# PCIE_PACKET_SWITCH.net
KiCad netlist of a schematic drawn in Altium Designer
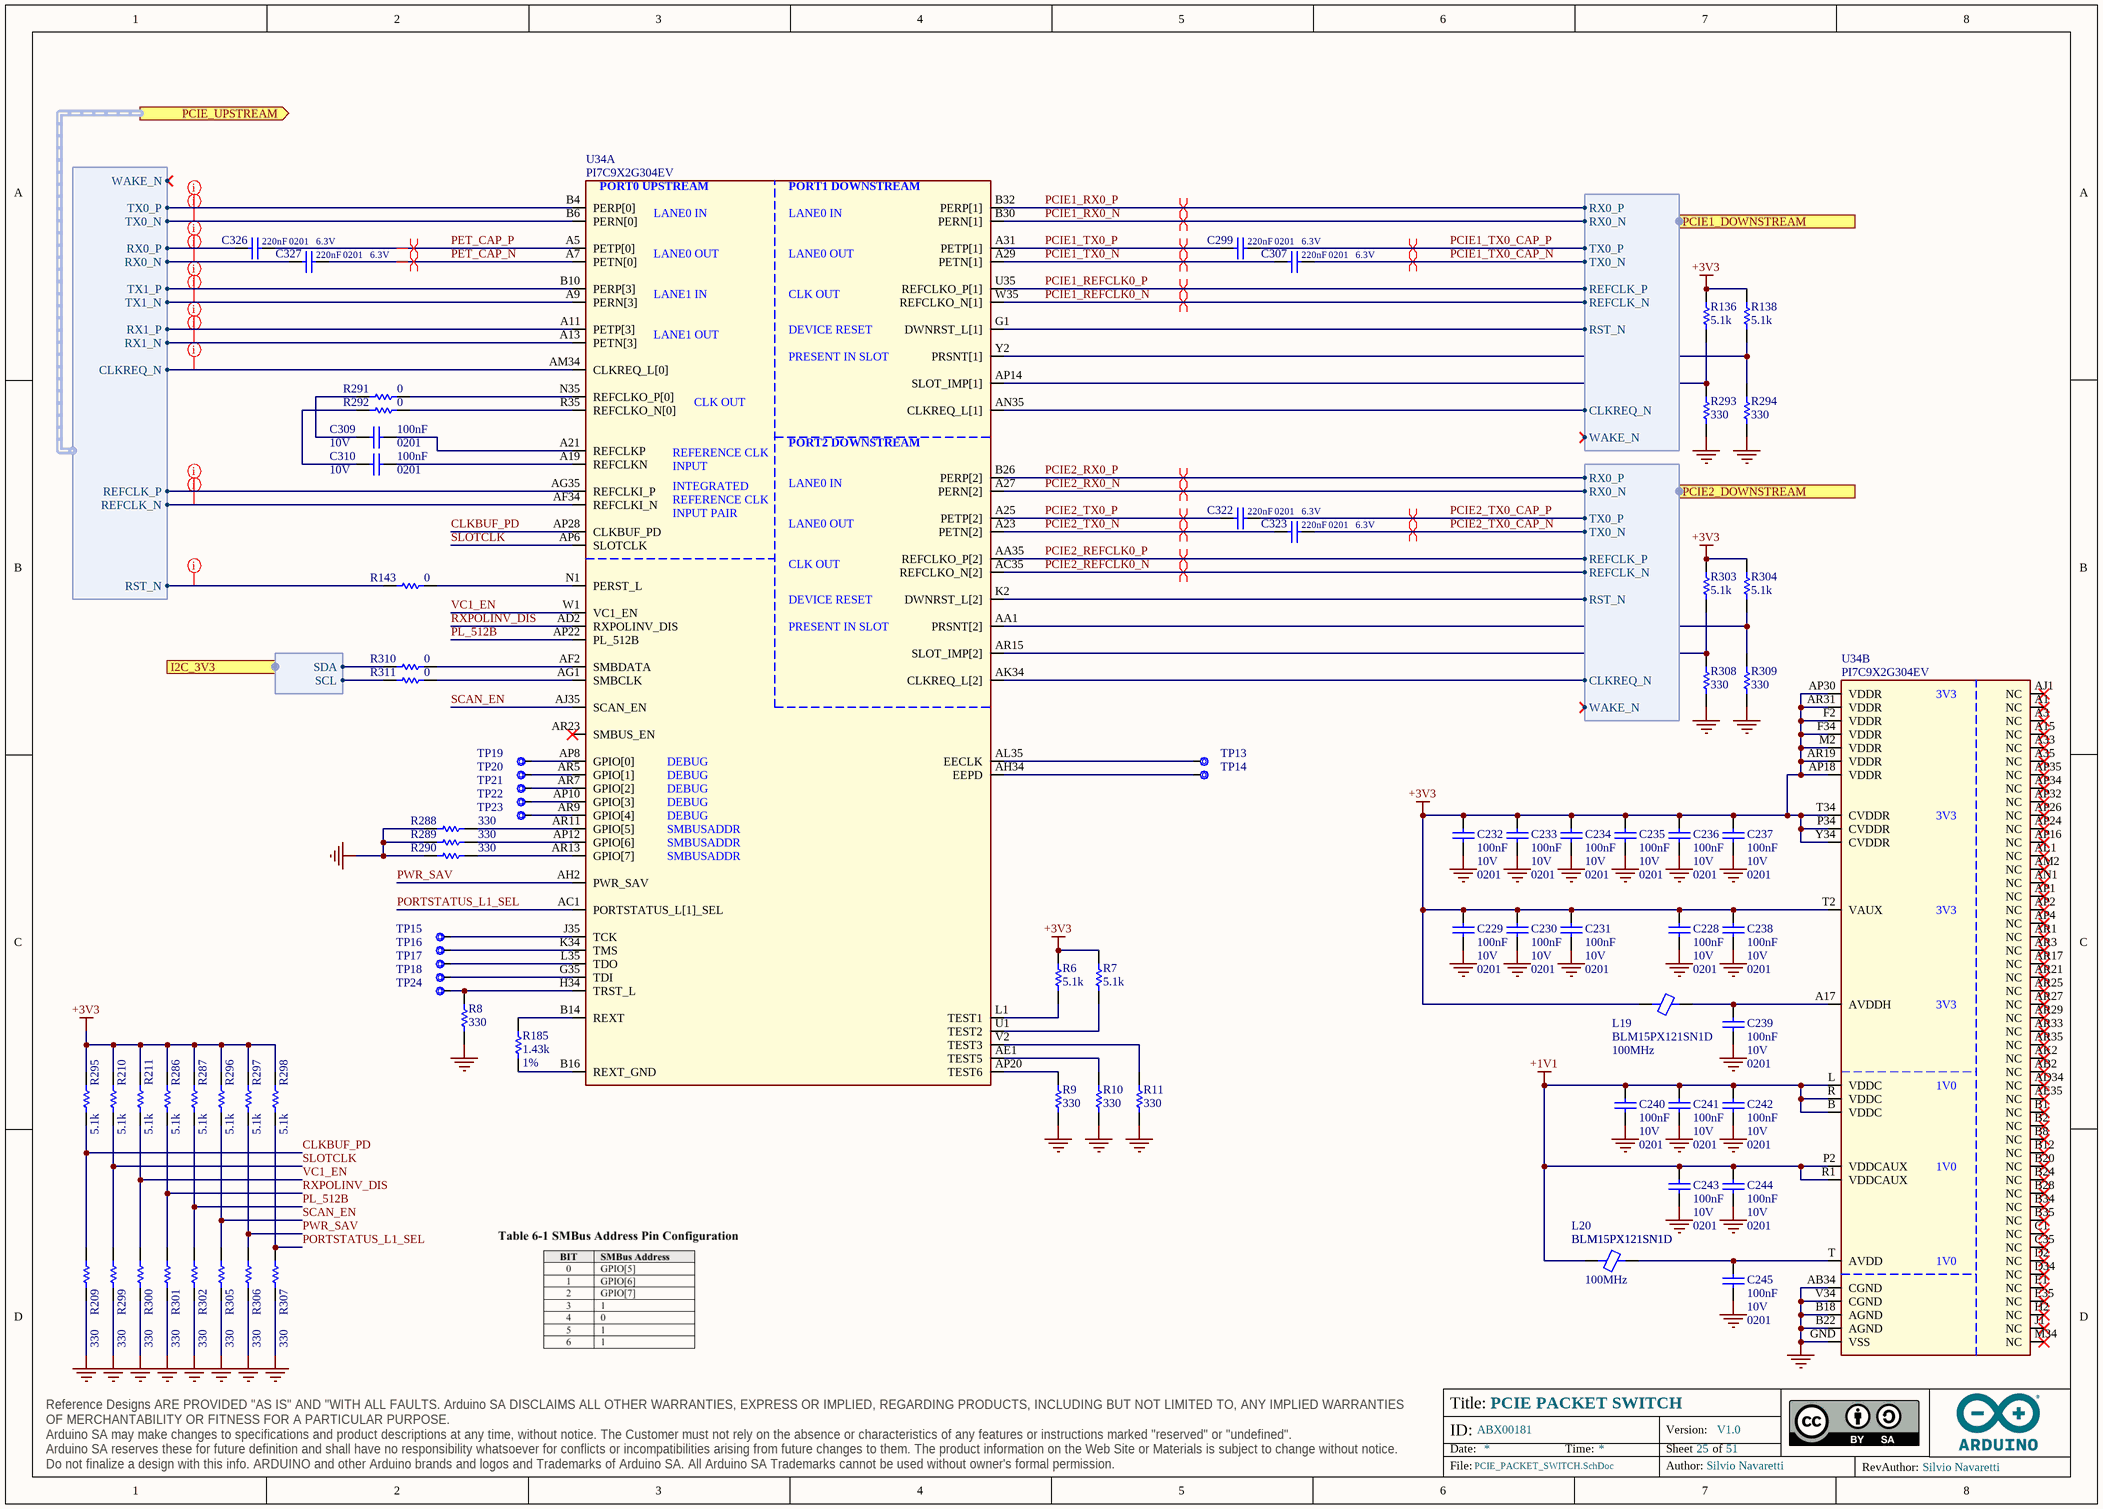
[diagram p0: PCIE_PACKET_SWITCH.SchDoc]

(export (version "E")
  (design (tool "Eeschema 10.0.6"))
  (components
    (comp (ref "C228")
      (value "100nF")
      (footprint "CAP-0201")
      (description "CAP CHIP 0201 100nF 10% 10V X5R")
      (fields
        (field (name "PART NUMBER") "CL03A104KP3NNNC")
        (field (name "MANUFACTURER") "Samsung Electro-Mechanics")
        (field (name "VOLTAGE") "10V")
        (field (name "CASE CODE (IMPERIAL)") "0201")
      )
      (libsource (lib "Clean") (part "CAP"))
    )
    (comp (ref "C229")
      (value "100nF")
      (footprint "CAP-0201")
      (description "CAP CHIP 0201 100nF 10% 10V X5R")
      (fields
        (field (name "PART NUMBER") "CL03A104KP3NNNC")
        (field (name "MANUFACTURER") "Samsung Electro-Mechanics")
        (field (name "VOLTAGE") "10V")
        (field (name "CASE CODE (IMPERIAL)") "0201")
      )
      (libsource (lib "Clean") (part "CAP"))
    )
    (comp (ref "C230")
      (value "100nF")
      (footprint "CAP-0201")
      (description "CAP CHIP 0201 100nF 10% 10V X5R")
      (fields
        (field (name "PART NUMBER") "CL03A104KP3NNNC")
        (field (name "MANUFACTURER") "Samsung Electro-Mechanics")
        (field (name "VOLTAGE") "10V")
        (field (name "CASE CODE (IMPERIAL)") "0201")
      )
      (libsource (lib "Clean") (part "CAP"))
    )
    (comp (ref "C231")
      (value "100nF")
      (footprint "CAP-0201")
      (description "CAP CHIP 0201 100nF 10% 10V X5R")
      (fields
        (field (name "PART NUMBER") "CL03A104KP3NNNC")
        (field (name "MANUFACTURER") "Samsung Electro-Mechanics")
        (field (name "VOLTAGE") "10V")
        (field (name "CASE CODE (IMPERIAL)") "0201")
      )
      (libsource (lib "Clean") (part "CAP"))
    )
    (comp (ref "C232")
      (value "100nF")
      (footprint "CAP-0201")
      (description "CAP CHIP 0201 100nF 10% 10V X5R")
      (fields
        (field (name "PART NUMBER") "CL03A104KP3NNNC")
        (field (name "MANUFACTURER") "Samsung Electro-Mechanics")
        (field (name "VOLTAGE") "10V")
        (field (name "CASE CODE (IMPERIAL)") "0201")
      )
      (libsource (lib "Clean") (part "CAP"))
    )
    (comp (ref "C233")
      (value "100nF")
      (footprint "CAP-0201")
      (description "CAP CHIP 0201 100nF 10% 10V X5R")
      (fields
        (field (name "PART NUMBER") "CL03A104KP3NNNC")
        (field (name "MANUFACTURER") "Samsung Electro-Mechanics")
        (field (name "VOLTAGE") "10V")
        (field (name "CASE CODE (IMPERIAL)") "0201")
      )
      (libsource (lib "Clean") (part "CAP"))
    )
    (comp (ref "C234")
      (value "100nF")
      (footprint "CAP-0201")
      (description "CAP CHIP 0201 100nF 10% 10V X5R")
      (fields
        (field (name "PART NUMBER") "CL03A104KP3NNNC")
        (field (name "MANUFACTURER") "Samsung Electro-Mechanics")
        (field (name "VOLTAGE") "10V")
        (field (name "CASE CODE (IMPERIAL)") "0201")
      )
      (libsource (lib "Clean") (part "CAP"))
    )
    (comp (ref "C235")
      (value "100nF")
      (footprint "CAP-0201")
      (description "CAP CHIP 0201 100nF 10% 10V X5R")
      (fields
        (field (name "PART NUMBER") "CL03A104KP3NNNC")
        (field (name "MANUFACTURER") "Samsung Electro-Mechanics")
        (field (name "VOLTAGE") "10V")
        (field (name "CASE CODE (IMPERIAL)") "0201")
      )
      (libsource (lib "Clean") (part "CAP"))
    )
    (comp (ref "C236")
      (value "100nF")
      (footprint "CAP-0201")
      (description "CAP CHIP 0201 100nF 10% 10V X5R")
      (fields
        (field (name "PART NUMBER") "CL03A104KP3NNNC")
        (field (name "MANUFACTURER") "Samsung Electro-Mechanics")
        (field (name "VOLTAGE") "10V")
        (field (name "CASE CODE (IMPERIAL)") "0201")
      )
      (libsource (lib "Clean") (part "CAP"))
    )
    (comp (ref "C237")
      (value "100nF")
      (footprint "CAP-0201")
      (description "CAP CHIP 0201 100nF 10% 10V X5R")
      (fields
        (field (name "PART NUMBER") "CL03A104KP3NNNC")
        (field (name "MANUFACTURER") "Samsung Electro-Mechanics")
        (field (name "VOLTAGE") "10V")
        (field (name "CASE CODE (IMPERIAL)") "0201")
      )
      (libsource (lib "Clean") (part "CAP"))
    )
    (comp (ref "C238")
      (value "100nF")
      (footprint "CAP-0201")
      (description "CAP CHIP 0201 100nF 10% 10V X5R")
      (fields
        (field (name "PART NUMBER") "CL03A104KP3NNNC")
        (field (name "MANUFACTURER") "Samsung Electro-Mechanics")
        (field (name "VOLTAGE") "10V")
        (field (name "CASE CODE (IMPERIAL)") "0201")
      )
      (libsource (lib "Clean") (part "CAP"))
    )
    (comp (ref "C239")
      (value "100nF")
      (footprint "CAP-0201")
      (description "CAP CHIP 0201 100nF 10% 10V X5R")
      (fields
        (field (name "PART NUMBER") "CL03A104KP3NNNC")
        (field (name "MANUFACTURER") "Samsung Electro-Mechanics")
        (field (name "VOLTAGE") "10V")
        (field (name "CASE CODE (IMPERIAL)") "0201")
      )
      (libsource (lib "Clean") (part "CAP"))
    )
    (comp (ref "C240")
      (value "100nF")
      (footprint "CAP-0201")
      (description "CAP CHIP 0201 100nF 10% 10V X5R")
      (fields
        (field (name "PART NUMBER") "CL03A104KP3NNNC")
        (field (name "MANUFACTURER") "Samsung Electro-Mechanics")
        (field (name "VOLTAGE") "10V")
        (field (name "CASE CODE (IMPERIAL)") "0201")
      )
      (libsource (lib "Clean") (part "CAP"))
    )
    (comp (ref "C241")
      (value "100nF")
      (footprint "CAP-0201")
      (description "CAP CHIP 0201 100nF 10% 10V X5R")
      (fields
        (field (name "PART NUMBER") "CL03A104KP3NNNC")
        (field (name "MANUFACTURER") "Samsung Electro-Mechanics")
        (field (name "VOLTAGE") "10V")
        (field (name "CASE CODE (IMPERIAL)") "0201")
      )
      (libsource (lib "Clean") (part "CAP"))
    )
    (comp (ref "C242")
      (value "100nF")
      (footprint "CAP-0201")
      (description "CAP CHIP 0201 100nF 10% 10V X5R")
      (fields
        (field (name "PART NUMBER") "CL03A104KP3NNNC")
        (field (name "MANUFACTURER") "Samsung Electro-Mechanics")
        (field (name "VOLTAGE") "10V")
        (field (name "CASE CODE (IMPERIAL)") "0201")
      )
      (libsource (lib "Clean") (part "CAP"))
    )
    (comp (ref "C243")
      (value "100nF")
      (footprint "CAP-0201")
      (description "CAP CHIP 0201 100nF 10% 10V X5R")
      (fields
        (field (name "PART NUMBER") "CL03A104KP3NNNC")
        (field (name "MANUFACTURER") "Samsung Electro-Mechanics")
        (field (name "VOLTAGE") "10V")
        (field (name "CASE CODE (IMPERIAL)") "0201")
      )
      (libsource (lib "Clean") (part "CAP"))
    )
    (comp (ref "C244")
      (value "100nF")
      (footprint "CAP-0201")
      (description "CAP CHIP 0201 100nF 10% 10V X5R")
      (fields
        (field (name "PART NUMBER") "CL03A104KP3NNNC")
        (field (name "MANUFACTURER") "Samsung Electro-Mechanics")
        (field (name "VOLTAGE") "10V")
        (field (name "CASE CODE (IMPERIAL)") "0201")
      )
      (libsource (lib "Clean") (part "CAP"))
    )
    (comp (ref "C245")
      (value "100nF")
      (footprint "CAP-0201")
      (description "CAP CHIP 0201 100nF 10% 10V X5R")
      (fields
        (field (name "PART NUMBER") "CL03A104KP3NNNC")
        (field (name "MANUFACTURER") "Samsung Electro-Mechanics")
        (field (name "VOLTAGE") "10V")
        (field (name "CASE CODE (IMPERIAL)") "0201")
      )
      (libsource (lib "Clean") (part "CAP"))
    )
    (comp (ref "C299")
      (value "220nF")
      (footprint "CAP-0201")
      (description "CAP CHIP 0201 220nF 20% 6.3V X5R")
      (fields
        (field (name "CASE CODE (IMPERIAL)") "0201")
        (field (name "TOLERANCE") "20%")
        (field (name "PART NUMBER") "GRM033R60J224ME15D")
        (field (name "VOLTAGE") "6.3V")
      )
      (libsource (lib "Clean") (part "CAP"))
    )
    (comp (ref "C307")
      (value "220nF")
      (footprint "CAP-0201")
      (description "CAP CHIP 0201 220nF 20% 6.3V X5R")
      (fields
        (field (name "CASE CODE (IMPERIAL)") "0201")
        (field (name "TOLERANCE") "20%")
        (field (name "PART NUMBER") "GRM033R60J224ME15D")
        (field (name "VOLTAGE") "6.3V")
      )
      (libsource (lib "Clean") (part "CAP"))
    )
    (comp (ref "C309")
      (value "100nF")
      (footprint "CAP-0201")
      (description "CAP CHIP 0201 100nF 10% 10V X5R")
      (fields
        (field (name "PART NUMBER") "CL03A104KP3NNNC")
        (field (name "MANUFACTURER") "Samsung Electro-Mechanics")
        (field (name "VOLTAGE") "10V")
        (field (name "CASE CODE (IMPERIAL)") "0201")
      )
      (libsource (lib "Clean") (part "CAP"))
    )
    (comp (ref "C310")
      (value "100nF")
      (footprint "CAP-0201")
      (description "CAP CHIP 0201 100nF 10% 10V X5R")
      (fields
        (field (name "PART NUMBER") "CL03A104KP3NNNC")
        (field (name "MANUFACTURER") "Samsung Electro-Mechanics")
        (field (name "VOLTAGE") "10V")
        (field (name "CASE CODE (IMPERIAL)") "0201")
      )
      (libsource (lib "Clean") (part "CAP"))
    )
    (comp (ref "C322")
      (value "220nF")
      (footprint "CAP-0201")
      (description "CAP CHIP 0201 220nF 20% 6.3V X5R")
      (fields
        (field (name "CASE CODE (IMPERIAL)") "0201")
        (field (name "TOLERANCE") "20%")
        (field (name "PART NUMBER") "GRM033R60J224ME15D")
        (field (name "VOLTAGE") "6.3V")
      )
      (libsource (lib "Clean") (part "CAP"))
    )
    (comp (ref "C323")
      (value "220nF")
      (footprint "CAP-0201")
      (description "CAP CHIP 0201 220nF 20% 6.3V X5R")
      (fields
        (field (name "CASE CODE (IMPERIAL)") "0201")
        (field (name "TOLERANCE") "20%")
        (field (name "PART NUMBER") "GRM033R60J224ME15D")
        (field (name "VOLTAGE") "6.3V")
      )
      (libsource (lib "Clean") (part "CAP"))
    )
    (comp (ref "C326")
      (value "220nF")
      (footprint "CAP-0201")
      (description "CAP CHIP 0201 220nF 20% 6.3V X5R")
      (fields
        (field (name "CASE CODE (IMPERIAL)") "0201")
        (field (name "TOLERANCE") "20%")
        (field (name "PART NUMBER") "GRM033R60J224ME15D")
        (field (name "VOLTAGE") "6.3V")
      )
      (libsource (lib "Clean") (part "CAP"))
    )
    (comp (ref "C327")
      (value "220nF")
      (footprint "CAP-0201")
      (description "CAP CHIP 0201 220nF 20% 6.3V X5R")
      (fields
        (field (name "CASE CODE (IMPERIAL)") "0201")
        (field (name "TOLERANCE") "20%")
        (field (name "PART NUMBER") "GRM033R60J224ME15D")
        (field (name "VOLTAGE") "6.3V")
      )
      (libsource (lib "Clean") (part "CAP"))
    )
    (comp (ref "L19")
      (value "BLM15PX121SN1D")
      (footprint "L-0402")
      (description "FERRITE SMD 0402 120Ohm 25% 100MHz Ferrite 2A")
      (fields
        (field (name "TEST FREQUENCY") "100MHz")
        (field (name "MANUFACTURER") "Murata")
        (field (name "TOLERANCE") "25%")
      )
      (libsource (lib "Clean") (part "Ferrite"))
    )
    (comp (ref "L20")
      (value "BLM15PX121SN1D")
      (footprint "L-0402")
      (description "FERRITE SMD 0402 120Ohm 25% 100MHz Ferrite 2A")
      (fields
        (field (name "PART NUMBER") "BLM15PX121SN1D")
        (field (name "TEST FREQUENCY") "100MHz")
        (field (name "MANUFACTURER") "Murata")
        (field (name "TOLERANCE") "25%")
      )
      (libsource (lib "Clean") (part "Ferrite"))
    )
    (comp (ref "R6")
      (value "5.1k")
      (footprint "RES-0201")
      (description "RES CHIP 0201 5k1 1% 1/20W")
      (fields (field (name "MANUFACTURER") "Panasonic") (field (name "PART NUMBER") "ERJ-1GNF5101C"))
      (libsource (lib "Clean") (part "RES"))
    )
    (comp (ref "R7")
      (value "5.1k")
      (footprint "RES-0201")
      (description "RES CHIP 0201 5k1 1% 1/20W")
      (fields (field (name "MANUFACTURER") "Panasonic") (field (name "PART NUMBER") "ERJ-1GNF5101C"))
      (libsource (lib "Clean") (part "RES"))
    )
    (comp (ref "R8")
      (value "330")
      (footprint "RES-0201")
      (description "RES CHIP 0201 330R 1% 1/20W")
      (fields (field (name "MANUFACTURER") "Yageo") (field (name "POWER") "50mW"))
      (libsource (lib "Clean") (part "RES"))
    )
    (comp (ref "R9")
      (value "330")
      (footprint "RES-0201")
      (description "RES CHIP 0201 330R 1% 1/20W")
      (fields (field (name "MANUFACTURER") "Yageo") (field (name "POWER") "50mW"))
      (libsource (lib "Clean") (part "RES"))
    )
    (comp (ref "R10")
      (value "330")
      (footprint "RES-0201")
      (description "RES CHIP 0201 330R 1% 1/20W")
      (fields (field (name "MANUFACTURER") "Yageo") (field (name "POWER") "50mW"))
      (libsource (lib "Clean") (part "RES"))
    )
    (comp (ref "R11")
      (value "330")
      (footprint "RES-0201")
      (description "RES CHIP 0201 330R 1% 1/20W")
      (fields (field (name "MANUFACTURER") "Yageo") (field (name "POWER") "50mW"))
      (libsource (lib "Clean") (part "RES"))
    )
    (comp (ref "R136")
      (value "5.1k")
      (footprint "RES-0201")
      (description "RES CHIP 0201 5k1 1% 1/20W")
      (fields (field (name "MANUFACTURER") "Panasonic") (field (name "PART NUMBER") "ERJ-1GNF5101C"))
      (libsource (lib "Clean") (part "RES"))
    )
    (comp (ref "R138")
      (value "5.1k")
      (footprint "RES-0201")
      (description "RES CHIP 0201 5k1 1% 1/20W")
      (fields (field (name "MANUFACTURER") "Panasonic") (field (name "PART NUMBER") "ERJ-1GNF5101C"))
      (libsource (lib "Clean") (part "RES"))
    )
    (comp (ref "R143")
      (value "0")
      (footprint "RES-0201")
      (description "RES CHIP 0201 0R")
      (fields (field (name "MANUFACTURER") "Vishay") (field (name "PART NUMBER") "CRCW02010000Z0ED"))
      (libsource (lib "Clean") (part "RES"))
    )
    (comp (ref "R185")
      (value "1.43k")
      (footprint "RES-0201")
      (description "RES CHIP 0201 1k43 1% 1/20W")
      (fields
        (field (name "TOLERANCE") "1%")
        (field (name "POWER") "50mW")
        (field (name "PART NUMBER") "RC0201FR-071K43L")
      )
      (libsource (lib "Clean") (part "RES"))
    )
    (comp (ref "R209")
      (value "330")
      (footprint "RES-0201")
      (description "RES CHIP 0201 330R 1% 1/20W")
      (fields (field (name "MANUFACTURER") "Yageo") (field (name "POWER") "50mW"))
      (libsource (lib "Clean") (part "RES"))
    )
    (comp (ref "R210")
      (value "5.1k")
      (footprint "RES-0201")
      (description "RES CHIP 0201 5k1 1% 1/20W")
      (fields (field (name "MANUFACTURER") "Panasonic") (field (name "PART NUMBER") "ERJ-1GNF5101C"))
      (libsource (lib "Clean") (part "RES"))
    )
    (comp (ref "R211")
      (value "5.1k")
      (footprint "RES-0201")
      (description "RES CHIP 0201 5k1 1% 1/20W")
      (fields (field (name "MANUFACTURER") "Panasonic") (field (name "PART NUMBER") "ERJ-1GNF5101C"))
      (libsource (lib "Clean") (part "RES"))
    )
    (comp (ref "R286")
      (value "5.1k")
      (footprint "RES-0201")
      (description "RES CHIP 0201 5k1 1% 1/20W")
      (fields (field (name "MANUFACTURER") "Panasonic") (field (name "PART NUMBER") "ERJ-1GNF5101C"))
      (libsource (lib "Clean") (part "RES"))
    )
    (comp (ref "R287")
      (value "5.1k")
      (footprint "RES-0201")
      (description "RES CHIP 0201 5k1 1% 1/20W")
      (fields (field (name "MANUFACTURER") "Panasonic") (field (name "PART NUMBER") "ERJ-1GNF5101C"))
      (libsource (lib "Clean") (part "RES"))
    )
    (comp (ref "R288")
      (value "330")
      (footprint "RES-0201")
      (description "RES CHIP 0201 330R 1% 1/20W")
      (fields (field (name "MANUFACTURER") "Yageo") (field (name "POWER") "50mW"))
      (libsource (lib "Clean") (part "RES"))
    )
    (comp (ref "R289")
      (value "330")
      (footprint "RES-0201")
      (description "RES CHIP 0201 330R 1% 1/20W")
      (fields (field (name "MANUFACTURER") "Yageo") (field (name "POWER") "50mW"))
      (libsource (lib "Clean") (part "RES"))
    )
    (comp (ref "R290")
      (value "330")
      (footprint "RES-0201")
      (description "RES CHIP 0201 330R 1% 1/20W")
      (fields (field (name "MANUFACTURER") "Yageo") (field (name "POWER") "50mW"))
      (libsource (lib "Clean") (part "RES"))
    )
    (comp (ref "R291")
      (value "0")
      (footprint "RES-0201")
      (description "RES CHIP 0201 0R")
      (fields (field (name "MANUFACTURER") "Vishay") (field (name "PART NUMBER") "CRCW02010000Z0ED"))
      (libsource (lib "Clean") (part "RES"))
    )
    (comp (ref "R292")
      (value "0")
      (footprint "RES-0201")
      (description "RES CHIP 0201 0R")
      (fields (field (name "MANUFACTURER") "Vishay") (field (name "PART NUMBER") "CRCW02010000Z0ED"))
      (libsource (lib "Clean") (part "RES"))
    )
    (comp (ref "R293")
      (value "330")
      (footprint "RES-0201")
      (description "RES CHIP 0201 330R 1% 1/20W")
      (fields (field (name "MANUFACTURER") "Yageo") (field (name "POWER") "50mW"))
      (libsource (lib "Clean") (part "RES"))
    )
    (comp (ref "R294")
      (value "330")
      (footprint "RES-0201")
      (description "RES CHIP 0201 330R 1% 1/20W")
      (fields (field (name "MANUFACTURER") "Yageo") (field (name "POWER") "50mW"))
      (libsource (lib "Clean") (part "RES"))
    )
    (comp (ref "R295")
      (value "5.1k")
      (footprint "RES-0201")
      (description "RES CHIP 0201 5k1 1% 1/20W")
      (fields (field (name "MANUFACTURER") "Panasonic") (field (name "PART NUMBER") "ERJ-1GNF5101C"))
      (libsource (lib "Clean") (part "RES"))
    )
    (comp (ref "R296")
      (value "5.1k")
      (footprint "RES-0201")
      (description "RES CHIP 0201 5k1 1% 1/20W")
      (fields (field (name "MANUFACTURER") "Panasonic") (field (name "PART NUMBER") "ERJ-1GNF5101C"))
      (libsource (lib "Clean") (part "RES"))
    )
    (comp (ref "R297")
      (value "5.1k")
      (footprint "RES-0201")
      (description "RES CHIP 0201 5k1 1% 1/20W")
      (fields (field (name "MANUFACTURER") "Panasonic") (field (name "PART NUMBER") "ERJ-1GNF5101C"))
      (libsource (lib "Clean") (part "RES"))
    )
    (comp (ref "R298")
      (value "5.1k")
      (footprint "RES-0201")
      (description "RES CHIP 0201 5k1 1% 1/20W")
      (fields (field (name "MANUFACTURER") "Panasonic") (field (name "PART NUMBER") "ERJ-1GNF5101C"))
      (libsource (lib "Clean") (part "RES"))
    )
    (comp (ref "R299")
      (value "330")
      (footprint "RES-0201")
      (description "RES CHIP 0201 330R 1% 1/20W")
      (fields (field (name "MANUFACTURER") "Yageo") (field (name "POWER") "50mW"))
      (libsource (lib "Clean") (part "RES"))
    )
    (comp (ref "R300")
      (value "330")
      (footprint "RES-0201")
      (description "RES CHIP 0201 330R 1% 1/20W")
      (fields (field (name "MANUFACTURER") "Yageo") (field (name "POWER") "50mW"))
      (libsource (lib "Clean") (part "RES"))
    )
    (comp (ref "R301")
      (value "330")
      (footprint "RES-0201")
      (description "RES CHIP 0201 330R 1% 1/20W")
      (fields (field (name "MANUFACTURER") "Yageo") (field (name "POWER") "50mW"))
      (libsource (lib "Clean") (part "RES"))
    )
    (comp (ref "R302")
      (value "330")
      (footprint "RES-0201")
      (description "RES CHIP 0201 330R 1% 1/20W")
      (fields (field (name "MANUFACTURER") "Yageo") (field (name "POWER") "50mW"))
      (libsource (lib "Clean") (part "RES"))
    )
    (comp (ref "R303")
      (value "5.1k")
      (footprint "RES-0201")
      (description "RES CHIP 0201 5k1 1% 1/20W")
      (fields (field (name "MANUFACTURER") "Panasonic") (field (name "PART NUMBER") "ERJ-1GNF5101C"))
      (libsource (lib "Clean") (part "RES"))
    )
    (comp (ref "R304")
      (value "5.1k")
      (footprint "RES-0201")
      (description "RES CHIP 0201 5k1 1% 1/20W")
      (fields (field (name "MANUFACTURER") "Panasonic") (field (name "PART NUMBER") "ERJ-1GNF5101C"))
      (libsource (lib "Clean") (part "RES"))
    )
    (comp (ref "R305")
      (value "330")
      (footprint "RES-0201")
      (description "RES CHIP 0201 330R 1% 1/20W")
      (fields (field (name "MANUFACTURER") "Yageo") (field (name "POWER") "50mW"))
      (libsource (lib "Clean") (part "RES"))
    )
    (comp (ref "R306")
      (value "330")
      (footprint "RES-0201")
      (description "RES CHIP 0201 330R 1% 1/20W")
      (fields (field (name "MANUFACTURER") "Yageo") (field (name "POWER") "50mW"))
      (libsource (lib "Clean") (part "RES"))
    )
    (comp (ref "R307")
      (value "330")
      (footprint "RES-0201")
      (description "RES CHIP 0201 330R 1% 1/20W")
      (fields (field (name "MANUFACTURER") "Yageo") (field (name "POWER") "50mW"))
      (libsource (lib "Clean") (part "RES"))
    )
    (comp (ref "R308")
      (value "330")
      (footprint "RES-0201")
      (description "RES CHIP 0201 330R 1% 1/20W")
      (fields (field (name "MANUFACTURER") "Yageo") (field (name "POWER") "50mW"))
      (libsource (lib "Clean") (part "RES"))
    )
    (comp (ref "R309")
      (value "330")
      (footprint "RES-0201")
      (description "RES CHIP 0201 330R 1% 1/20W")
      (fields (field (name "MANUFACTURER") "Yageo") (field (name "POWER") "50mW"))
      (libsource (lib "Clean") (part "RES"))
    )
    (comp (ref "R310")
      (value "0")
      (footprint "RES-0201")
      (description "RES CHIP 0201 0R")
      (fields (field (name "MANUFACTURER") "Vishay") (field (name "PART NUMBER") "CRCW02010000Z0ED"))
      (libsource (lib "Clean") (part "RES"))
    )
    (comp (ref "R311")
      (value "0")
      (footprint "RES-0201")
      (description "RES CHIP 0201 0R")
      (fields (field (name "MANUFACTURER") "Vishay") (field (name "PART NUMBER") "CRCW02010000Z0ED"))
      (libsource (lib "Clean") (part "RES"))
    )
    (comp (ref "TP13")
      (value "Test point 1.00mm")
      (footprint "TP-1.00MM")
      (fields (field (name "PART NUMBER") "This is not a component"))
      (libsource (lib "Clean") (part "TESTPOINT"))
    )
    (comp (ref "TP14")
      (value "Test point 1.00mm")
      (footprint "TP-1.00MM")
      (fields (field (name "PART NUMBER") "This is not a component"))
      (libsource (lib "Clean") (part "TESTPOINT"))
    )
    (comp (ref "TP15")
      (value "Test point 1.00mm")
      (footprint "TP-1.00MM")
      (fields (field (name "PART NUMBER") "This is not a component"))
      (libsource (lib "Clean") (part "TESTPOINT"))
    )
    (comp (ref "TP16")
      (value "Test point 1.00mm")
      (footprint "TP-1.00MM")
      (fields (field (name "PART NUMBER") "This is not a component"))
      (libsource (lib "Clean") (part "TESTPOINT"))
    )
    (comp (ref "TP17")
      (value "Test point 1.00mm")
      (footprint "TP-1.00MM")
      (fields (field (name "PART NUMBER") "This is not a component"))
      (libsource (lib "Clean") (part "TESTPOINT"))
    )
    (comp (ref "TP18")
      (value "Test point 1.00mm")
      (footprint "TP-1.00MM")
      (fields (field (name "PART NUMBER") "This is not a component"))
      (libsource (lib "Clean") (part "TESTPOINT"))
    )
    (comp (ref "TP19")
      (value "Test point 1.00mm")
      (footprint "TP-1.00MM")
      (fields (field (name "PART NUMBER") "This is not a component"))
      (libsource (lib "Clean") (part "TESTPOINT"))
    )
    (comp (ref "TP20")
      (value "Test point 1.00mm")
      (footprint "TP-1.00MM")
      (fields (field (name "PART NUMBER") "This is not a component"))
      (libsource (lib "Clean") (part "TESTPOINT"))
    )
    (comp (ref "TP21")
      (value "Test point 1.00mm")
      (footprint "TP-1.00MM")
      (fields (field (name "PART NUMBER") "This is not a component"))
      (libsource (lib "Clean") (part "TESTPOINT"))
    )
    (comp (ref "TP22")
      (value "Test point 1.00mm")
      (footprint "TP-1.00MM")
      (fields (field (name "PART NUMBER") "This is not a component"))
      (libsource (lib "Clean") (part "TESTPOINT"))
    )
    (comp (ref "TP23")
      (value "Test point 1.00mm")
      (footprint "TP-1.00MM")
      (fields (field (name "PART NUMBER") "This is not a component"))
      (libsource (lib "Clean") (part "TESTPOINT"))
    )
    (comp (ref "TP24")
      (value "Test point 1.00mm")
      (footprint "TP-1.00MM")
      (fields (field (name "PART NUMBER") "This is not a component"))
      (libsource (lib "Clean") (part "TESTPOINT"))
    )
    (comp (ref "U34")
      (value "PI7C9X2G304EV")
      (footprint "PI7C9X2G304EV-Footprint-1")
      (description "IC 3PCIe 2.0 Packet Switch 3-Port, 4-Lane aQFN136 10x10mm")
      (fields (field (name "MANUFACTURER") "Diodes Incorporated"))
      (libsource (lib "Clean") (part "PI7C9X2G304EV"))
    )
  )
  (nets
    (net (code "4") (name "+1V1") (class "Default")
      (node (ref "C240") (pin "2") (pinfunction "2_2") (pintype "passive"))
      (node (ref "C241") (pin "2") (pinfunction "2_2") (pintype "passive"))
      (node (ref "C242") (pin "2") (pinfunction "2_2") (pintype "passive"))
      (node (ref "C243") (pin "2") (pinfunction "2_2") (pintype "passive"))
      (node (ref "C244") (pin "2") (pinfunction "2_2") (pintype "passive"))
      (node (ref "L20") (pin "1") (pinfunction "1_1") (pintype "passive"))
      (node (ref "U34") (pin "B") (pinfunction "VDDC_B") (pintype "passive"))
      (node (ref "U34") (pin "L") (pinfunction "VDDC_L") (pintype "passive"))
      (node (ref "U34") (pin "P2") (pinfunction "VDDCAUX_P2") (pintype "passive"))
      (node (ref "U34") (pin "R") (pinfunction "VDDC_R") (pintype "passive"))
      (node (ref "U34") (pin "R1") (pinfunction "VDDCAUX_R1") (pintype "passive"))
    )
    (net (code "5") (name "+3V3") (class "Default")
      (node (ref "C228") (pin "2") (pinfunction "2_2") (pintype "passive"))
      (node (ref "C229") (pin "2") (pinfunction "2_2") (pintype "passive"))
      (node (ref "C230") (pin "2") (pinfunction "2_2") (pintype "passive"))
      (node (ref "C231") (pin "2") (pinfunction "2_2") (pintype "passive"))
      (node (ref "C232") (pin "2") (pinfunction "2_2") (pintype "passive"))
      (node (ref "C233") (pin "2") (pinfunction "2_2") (pintype "passive"))
      (node (ref "C234") (pin "2") (pinfunction "2_2") (pintype "passive"))
      (node (ref "C235") (pin "2") (pinfunction "2_2") (pintype "passive"))
      (node (ref "C236") (pin "2") (pinfunction "2_2") (pintype "passive"))
      (node (ref "C237") (pin "2") (pinfunction "2_2") (pintype "passive"))
      (node (ref "C238") (pin "2") (pinfunction "2_2") (pintype "passive"))
      (node (ref "L19") (pin "1") (pinfunction "1_1") (pintype "passive"))
      (node (ref "R136") (pin "2") (pinfunction "2_2") (pintype "passive"))
      (node (ref "R138") (pin "2") (pinfunction "2_2") (pintype "passive"))
      (node (ref "R210") (pin "2") (pinfunction "2_2") (pintype "passive"))
      (node (ref "R211") (pin "2") (pinfunction "2_2") (pintype "passive"))
      (node (ref "R286") (pin "2") (pinfunction "2_2") (pintype "passive"))
      (node (ref "R287") (pin "2") (pinfunction "2_2") (pintype "passive"))
      (node (ref "R295") (pin "2") (pinfunction "2_2") (pintype "passive"))
      (node (ref "R296") (pin "2") (pinfunction "2_2") (pintype "passive"))
      (node (ref "R297") (pin "2") (pinfunction "2_2") (pintype "passive"))
      (node (ref "R298") (pin "2") (pinfunction "2_2") (pintype "passive"))
      (node (ref "R303") (pin "2") (pinfunction "2_2") (pintype "passive"))
      (node (ref "R304") (pin "2") (pinfunction "2_2") (pintype "passive"))
      (node (ref "R6") (pin "2") (pinfunction "2_2") (pintype "passive"))
      (node (ref "R7") (pin "2") (pinfunction "2_2") (pintype "passive"))
      (node (ref "U34") (pin "AP18") (pinfunction "VDDR_AP18") (pintype "passive"))
      (node (ref "U34") (pin "AP30") (pinfunction "VDDR_AP30") (pintype "passive"))
      (node (ref "U34") (pin "AR19") (pinfunction "VDDR_AR19") (pintype "passive"))
      (node (ref "U34") (pin "AR31") (pinfunction "VDDR_AR31") (pintype "passive"))
      (node (ref "U34") (pin "F2") (pinfunction "VDDR_F2") (pintype "passive"))
      (node (ref "U34") (pin "F34") (pinfunction "VDDR_F34") (pintype "passive"))
      (node (ref "U34") (pin "M2") (pinfunction "VDDR_M2") (pintype "passive"))
      (node (ref "U34") (pin "P34") (pinfunction "CVDDR_P34") (pintype "passive"))
      (node (ref "U34") (pin "T2") (pinfunction "VAUX_T2") (pintype "passive"))
      (node (ref "U34") (pin "T34") (pinfunction "CVDDR_T34") (pintype "passive"))
      (node (ref "U34") (pin "Y34") (pinfunction "CVDDR_Y34") (pintype "passive"))
    )
    (net (code "6") (name "/CLKBUF_PD") (class "Default")
      (node (ref "R209") (pin "2") (pinfunction "2_2") (pintype "passive"))
      (node (ref "R295") (pin "1") (pinfunction "1_1") (pintype "passive"))
      (node (ref "U34") (pin "AP28") (pinfunction "CLKBUF_PD_AP28") (pintype "passive"))
    )
    (net (code "7") (name "/PCIE1_REFCLK0_N") (class "Default")
      (node (ref "U34") (pin "W35") (pinfunction "REFCLKO_N[1]_W35") (pintype "passive"))
    )
    (net (code "8") (name "/PCIE1_REFCLK0_P") (class "Default")
      (node (ref "U34") (pin "U35") (pinfunction "REFCLKO_P[1]_U35") (pintype "passive"))
    )
    (net (code "9") (name "/PCIE1_RX0_N") (class "Default")
      (node (ref "U34") (pin "B30") (pinfunction "PERN[1]_B30") (pintype "passive"))
    )
    (net (code "10") (name "/PCIE1_RX0_P") (class "Default")
      (node (ref "U34") (pin "B32") (pinfunction "PERP[1]_B32") (pintype "passive"))
    )
    (net (code "11") (name "/PCIE1_TX0_CAP_N") (class "Default")
      (node (ref "C307") (pin "1") (pinfunction "1_1") (pintype "passive"))
    )
    (net (code "12") (name "/PCIE1_TX0_CAP_P") (class "Default")
      (node (ref "C299") (pin "1") (pinfunction "1_1") (pintype "passive"))
    )
    (net (code "13") (name "/PCIE1_TX0_N") (class "Default")
      (node (ref "C307") (pin "2") (pinfunction "2_2") (pintype "passive"))
      (node (ref "U34") (pin "A29") (pinfunction "PETN[1]_A29") (pintype "passive"))
    )
    (net (code "14") (name "/PCIE1_TX0_P") (class "Default")
      (node (ref "C299") (pin "2") (pinfunction "2_2") (pintype "passive"))
      (node (ref "U34") (pin "A31") (pinfunction "PETP[1]_A31") (pintype "passive"))
    )
    (net (code "15") (name "/PCIE2_REFCLK0_N") (class "Default")
      (node (ref "U34") (pin "AC35") (pinfunction "REFCLKO_N[2]_AC35") (pintype "passive"))
    )
    (net (code "16") (name "/PCIE2_REFCLK0_P") (class "Default")
      (node (ref "U34") (pin "AA35") (pinfunction "REFCLKO_P[2]_AA35") (pintype "passive"))
    )
    (net (code "17") (name "/PCIE2_RX0_N") (class "Default")
      (node (ref "U34") (pin "A27") (pinfunction "PERN[2]_A27") (pintype "passive"))
    )
    (net (code "18") (name "/PCIE2_RX0_P") (class "Default")
      (node (ref "U34") (pin "B26") (pinfunction "PERP[2]_B26") (pintype "passive"))
    )
    (net (code "19") (name "/PCIE2_TX0_CAP_N") (class "Default")
      (node (ref "C323") (pin "1") (pinfunction "1_1") (pintype "passive"))
    )
    (net (code "20") (name "/PCIE2_TX0_CAP_P") (class "Default")
      (node (ref "C322") (pin "1") (pinfunction "1_1") (pintype "passive"))
    )
    (net (code "21") (name "/PCIE2_TX0_N") (class "Default")
      (node (ref "C323") (pin "2") (pinfunction "2_2") (pintype "passive"))
      (node (ref "U34") (pin "A23") (pinfunction "PETN[2]_A23") (pintype "passive"))
    )
    (net (code "22") (name "/PCIE2_TX0_P") (class "Default")
      (node (ref "C322") (pin "2") (pinfunction "2_2") (pintype "passive"))
      (node (ref "U34") (pin "A25") (pinfunction "PETP[2]_A25") (pintype "passive"))
    )
    (net (code "23") (name "/PET_CAP_N") (class "Default")
      (node (ref "C327") (pin "1") (pinfunction "1_1") (pintype "passive"))
      (node (ref "U34") (pin "A7") (pinfunction "PETN[0]_A7") (pintype "passive"))
    )
    (net (code "24") (name "/PET_CAP_P") (class "Default")
      (node (ref "C326") (pin "1") (pinfunction "1_1") (pintype "passive"))
      (node (ref "U34") (pin "A5") (pinfunction "PETP[0]_A5") (pintype "passive"))
    )
    (net (code "25") (name "/PL_512B") (class "Default")
      (node (ref "R287") (pin "1") (pinfunction "1_1") (pintype "passive"))
      (node (ref "R302") (pin "2") (pinfunction "2_2") (pintype "passive"))
      (node (ref "U34") (pin "AP22") (pinfunction "PL_512B_AP22") (pintype "passive"))
    )
    (net (code "26") (name "/PORTSTATUS_L1_SEL") (class "Default")
      (node (ref "R298") (pin "1") (pinfunction "1_1") (pintype "passive"))
      (node (ref "R307") (pin "2") (pinfunction "2_2") (pintype "passive"))
      (node (ref "U34") (pin "AC1") (pinfunction "PORTSTATUS_L[1]_SEL_AC1") (pintype "passive"))
    )
    (net (code "27") (name "/PWR_SAV") (class "Default")
      (node (ref "R297") (pin "1") (pinfunction "1_1") (pintype "passive"))
      (node (ref "R306") (pin "2") (pinfunction "2_2") (pintype "passive"))
      (node (ref "U34") (pin "AH2") (pinfunction "PWR_SAV_AH2") (pintype "passive"))
    )
    (net (code "28") (name "/RX1_N") (class "Default")
      (node (ref "U34") (pin "A13") (pinfunction "PETN[3]_A13") (pintype "passive"))
    )
    (net (code "29") (name "/RX1_P") (class "Default")
      (node (ref "U34") (pin "A11") (pinfunction "PETP[3]_A11") (pintype "passive"))
    )
    (net (code "30") (name "/RXPOLINV_DIS") (class "Default")
      (node (ref "R286") (pin "1") (pinfunction "1_1") (pintype "passive"))
      (node (ref "R301") (pin "2") (pinfunction "2_2") (pintype "passive"))
      (node (ref "U34") (pin "AD2") (pinfunction "RXPOLINV_DIS_AD2") (pintype "passive"))
    )
    (net (code "31") (name "/SCAN_EN") (class "Default")
      (node (ref "R296") (pin "1") (pinfunction "1_1") (pintype "passive"))
      (node (ref "R305") (pin "2") (pinfunction "2_2") (pintype "passive"))
      (node (ref "U34") (pin "AJ35") (pinfunction "SCAN_EN_AJ35") (pintype "passive"))
    )
    (net (code "32") (name "/SCL") (class "Default")
      (node (ref "R311") (pin "2") (pinfunction "2_2") (pintype "passive"))
    )
    (net (code "33") (name "/SDA") (class "Default")
      (node (ref "R310") (pin "2") (pinfunction "2_2") (pintype "passive"))
    )
    (net (code "34") (name "/SLOTCLK") (class "Default")
      (node (ref "R210") (pin "1") (pinfunction "1_1") (pintype "passive"))
      (node (ref "R299") (pin "2") (pinfunction "2_2") (pintype "passive"))
      (node (ref "U34") (pin "AP6") (pinfunction "SLOTCLK_AP6") (pintype "passive"))
    )
    (net (code "35") (name "/TX1_N") (class "Default")
      (node (ref "U34") (pin "A9") (pinfunction "PERN[3]_A9") (pintype "passive"))
    )
    (net (code "36") (name "/TX1_P") (class "Default")
      (node (ref "U34") (pin "B10") (pinfunction "PERP[3]_B10") (pintype "passive"))
    )
    (net (code "37") (name "/VC1_EN") (class "Default")
      (node (ref "R211") (pin "1") (pinfunction "1_1") (pintype "passive"))
      (node (ref "R300") (pin "2") (pinfunction "2_2") (pintype "passive"))
      (node (ref "U34") (pin "W1") (pinfunction "VC1_EN_W1") (pintype "passive"))
    )
    (net (code "41") (name "GND") (class "Default")
      (node (ref "C228") (pin "1") (pinfunction "1_1") (pintype "passive"))
      (node (ref "C229") (pin "1") (pinfunction "1_1") (pintype "passive"))
      (node (ref "C230") (pin "1") (pinfunction "1_1") (pintype "passive"))
      (node (ref "C231") (pin "1") (pinfunction "1_1") (pintype "passive"))
      (node (ref "C232") (pin "1") (pinfunction "1_1") (pintype "passive"))
      (node (ref "C233") (pin "1") (pinfunction "1_1") (pintype "passive"))
      (node (ref "C234") (pin "1") (pinfunction "1_1") (pintype "passive"))
      (node (ref "C235") (pin "1") (pinfunction "1_1") (pintype "passive"))
      (node (ref "C236") (pin "1") (pinfunction "1_1") (pintype "passive"))
      (node (ref "C237") (pin "1") (pinfunction "1_1") (pintype "passive"))
      (node (ref "C238") (pin "1") (pinfunction "1_1") (pintype "passive"))
      (node (ref "C239") (pin "1") (pinfunction "1_1") (pintype "passive"))
      (node (ref "C240") (pin "1") (pinfunction "1_1") (pintype "passive"))
      (node (ref "C241") (pin "1") (pinfunction "1_1") (pintype "passive"))
      (node (ref "C242") (pin "1") (pinfunction "1_1") (pintype "passive"))
      (node (ref "C243") (pin "1") (pinfunction "1_1") (pintype "passive"))
      (node (ref "C244") (pin "1") (pinfunction "1_1") (pintype "passive"))
      (node (ref "C245") (pin "1") (pinfunction "1_1") (pintype "passive"))
      (node (ref "R10") (pin "1") (pinfunction "1_1") (pintype "passive"))
      (node (ref "R11") (pin "1") (pinfunction "1_1") (pintype "passive"))
      (node (ref "R209") (pin "1") (pinfunction "1_1") (pintype "passive"))
      (node (ref "R288") (pin "2") (pinfunction "2_2") (pintype "passive"))
      (node (ref "R289") (pin "2") (pinfunction "2_2") (pintype "passive"))
      (node (ref "R290") (pin "2") (pinfunction "2_2") (pintype "passive"))
      (node (ref "R293") (pin "1") (pinfunction "1_1") (pintype "passive"))
      (node (ref "R294") (pin "1") (pinfunction "1_1") (pintype "passive"))
      (node (ref "R299") (pin "1") (pinfunction "1_1") (pintype "passive"))
      (node (ref "R300") (pin "1") (pinfunction "1_1") (pintype "passive"))
      (node (ref "R301") (pin "1") (pinfunction "1_1") (pintype "passive"))
      (node (ref "R302") (pin "1") (pinfunction "1_1") (pintype "passive"))
      (node (ref "R305") (pin "1") (pinfunction "1_1") (pintype "passive"))
      (node (ref "R306") (pin "1") (pinfunction "1_1") (pintype "passive"))
      (node (ref "R307") (pin "1") (pinfunction "1_1") (pintype "passive"))
      (node (ref "R308") (pin "1") (pinfunction "1_1") (pintype "passive"))
      (node (ref "R309") (pin "1") (pinfunction "1_1") (pintype "passive"))
      (node (ref "R8") (pin "1") (pinfunction "1_1") (pintype "passive"))
      (node (ref "R9") (pin "1") (pinfunction "1_1") (pintype "passive"))
      (node (ref "U34") (pin "AB34") (pinfunction "CGND_AB34") (pintype "passive"))
      (node (ref "U34") (pin "B18") (pinfunction "AGND_B18") (pintype "passive"))
      (node (ref "U34") (pin "B22") (pinfunction "AGND_B22") (pintype "passive"))
      (node (ref "U34") (pin "GND") (pinfunction "VSS_GND") (pintype "passive"))
      (node (ref "U34") (pin "V34") (pinfunction "CGND_V34") (pintype "passive"))
    )
    (net (code "42") (name "Net-(C309-Pad2)") (class "Default")
      (node (ref "C309") (pin "2") (pinfunction "2_2") (pintype "passive"))
      (node (ref "R291") (pin "1") (pinfunction "1_1") (pintype "passive"))
    )
    (net (code "43") (name "Net-(C310-Pad2)") (class "Default")
      (node (ref "C310") (pin "2") (pinfunction "2_2") (pintype "passive"))
      (node (ref "R292") (pin "1") (pinfunction "1_1") (pintype "passive"))
    )
    (net (code "44") (name "Net-(U34A-EECLK)") (class "Default")
      (node (ref "TP13") (pin "X") (pinfunction "X_X") (pintype "passive"))
      (node (ref "U34") (pin "AL35") (pinfunction "EECLK_AL35") (pintype "passive"))
    )
    (net (code "45") (name "Net-(U34A-EEPD)") (class "Default")
      (node (ref "TP14") (pin "X") (pinfunction "X_X") (pintype "passive"))
      (node (ref "U34") (pin "AH34") (pinfunction "EEPD_AH34") (pintype "passive"))
    )
    (net (code "46") (name "Net-(U34A-GPIO[0])") (class "Default")
      (node (ref "TP19") (pin "X") (pinfunction "X_X") (pintype "passive"))
      (node (ref "U34") (pin "AP8") (pinfunction "GPIO[0]_AP8") (pintype "passive"))
    )
    (net (code "47") (name "Net-(U34A-GPIO[1])") (class "Default")
      (node (ref "TP20") (pin "X") (pinfunction "X_X") (pintype "passive"))
      (node (ref "U34") (pin "AR5") (pinfunction "GPIO[1]_AR5") (pintype "passive"))
    )
    (net (code "48") (name "Net-(U34A-GPIO[2])") (class "Default")
      (node (ref "TP21") (pin "X") (pinfunction "X_X") (pintype "passive"))
      (node (ref "U34") (pin "AR7") (pinfunction "GPIO[2]_AR7") (pintype "passive"))
    )
    (net (code "49") (name "Net-(U34A-GPIO[3])") (class "Default")
      (node (ref "TP22") (pin "X") (pinfunction "X_X") (pintype "passive"))
      (node (ref "U34") (pin "AP10") (pinfunction "GPIO[3]_AP10") (pintype "passive"))
    )
    (net (code "50") (name "Net-(U34A-GPIO[4])") (class "Default")
      (node (ref "TP23") (pin "X") (pinfunction "X_X") (pintype "passive"))
      (node (ref "U34") (pin "AR9") (pinfunction "GPIO[4]_AR9") (pintype "passive"))
    )
    (net (code "51") (name "Net-(U34A-GPIO[5])") (class "Default")
      (node (ref "R288") (pin "1") (pinfunction "1_1") (pintype "passive"))
      (node (ref "U34") (pin "AR11") (pinfunction "GPIO[5]_AR11") (pintype "passive"))
    )
    (net (code "52") (name "Net-(U34A-GPIO[6])") (class "Default")
      (node (ref "R289") (pin "1") (pinfunction "1_1") (pintype "passive"))
      (node (ref "U34") (pin "AP12") (pinfunction "GPIO[6]_AP12") (pintype "passive"))
    )
    (net (code "53") (name "Net-(U34A-GPIO[7])") (class "Default")
      (node (ref "R290") (pin "1") (pinfunction "1_1") (pintype "passive"))
      (node (ref "U34") (pin "AR13") (pinfunction "GPIO[7]_AR13") (pintype "passive"))
    )
    (net (code "54") (name "Net-(U34A-PERST_L)") (class "Default")
      (node (ref "R143") (pin "1") (pinfunction "1_1") (pintype "passive"))
      (node (ref "U34") (pin "N1") (pinfunction "PERST_L_N1") (pintype "passive"))
    )
    (net (code "55") (name "Net-(U34A-PRSNT[1])") (class "Default")
      (node (ref "R138") (pin "1") (pinfunction "1_1") (pintype "passive"))
      (node (ref "R294") (pin "2") (pinfunction "2_2") (pintype "passive"))
      (node (ref "U34") (pin "Y2") (pinfunction "PRSNT[1]_Y2") (pintype "passive"))
    )
    (net (code "56") (name "Net-(U34A-PRSNT[2])") (class "Default")
      (node (ref "R304") (pin "1") (pinfunction "1_1") (pintype "passive"))
      (node (ref "R309") (pin "2") (pinfunction "2_2") (pintype "passive"))
      (node (ref "U34") (pin "AA1") (pinfunction "PRSNT[2]_AA1") (pintype "passive"))
    )
    (net (code "57") (name "Net-(U34A-REFCLKN)") (class "Default")
      (node (ref "C310") (pin "1") (pinfunction "1_1") (pintype "passive"))
      (node (ref "U34") (pin "A19") (pinfunction "REFCLKN_A19") (pintype "passive"))
    )
    (net (code "58") (name "Net-(U34A-REFCLKO_N[0])") (class "Default")
      (node (ref "R292") (pin "2") (pinfunction "2_2") (pintype "passive"))
      (node (ref "U34") (pin "R35") (pinfunction "REFCLKO_N[0]_R35") (pintype "passive"))
    )
    (net (code "59") (name "Net-(U34A-REFCLKO_P[0])") (class "Default")
      (node (ref "R291") (pin "2") (pinfunction "2_2") (pintype "passive"))
      (node (ref "U34") (pin "N35") (pinfunction "REFCLKO_P[0]_N35") (pintype "passive"))
    )
    (net (code "60") (name "Net-(U34A-REFCLKP)") (class "Default")
      (node (ref "C309") (pin "1") (pinfunction "1_1") (pintype "passive"))
      (node (ref "U34") (pin "A21") (pinfunction "REFCLKP_A21") (pintype "passive"))
    )
    (net (code "61") (name "Net-(U34A-REXT)") (class "Default")
      (node (ref "R185") (pin "1") (pinfunction "1_1") (pintype "passive"))
      (node (ref "U34") (pin "B14") (pinfunction "REXT_B14") (pintype "passive"))
    )
    (net (code "62") (name "Net-(U34A-REXT_GND)") (class "Default")
      (node (ref "R185") (pin "2") (pinfunction "2_2") (pintype "passive"))
      (node (ref "U34") (pin "B16") (pinfunction "REXT_GND_B16") (pintype "passive"))
    )
    (net (code "63") (name "Net-(U34A-SLOT_IMP[1])") (class "Default")
      (node (ref "R136") (pin "1") (pinfunction "1_1") (pintype "passive"))
      (node (ref "R293") (pin "2") (pinfunction "2_2") (pintype "passive"))
      (node (ref "U34") (pin "AP14") (pinfunction "SLOT_IMP[1]_AP14") (pintype "passive"))
    )
    (net (code "64") (name "Net-(U34A-SLOT_IMP[2])") (class "Default")
      (node (ref "R303") (pin "1") (pinfunction "1_1") (pintype "passive"))
      (node (ref "R308") (pin "2") (pinfunction "2_2") (pintype "passive"))
      (node (ref "U34") (pin "AR15") (pinfunction "SLOT_IMP[2]_AR15") (pintype "passive"))
    )
    (net (code "65") (name "Net-(U34A-SMBCLK)") (class "Default")
      (node (ref "R311") (pin "1") (pinfunction "1_1") (pintype "passive"))
      (node (ref "U34") (pin "AG1") (pinfunction "SMBCLK_AG1") (pintype "passive"))
    )
    (net (code "66") (name "Net-(U34A-SMBDATA)") (class "Default")
      (node (ref "R310") (pin "1") (pinfunction "1_1") (pintype "passive"))
      (node (ref "U34") (pin "AF2") (pinfunction "SMBDATA_AF2") (pintype "passive"))
    )
    (net (code "67") (name "Net-(U34A-TCK)") (class "Default")
      (node (ref "TP15") (pin "X") (pinfunction "X_X") (pintype "passive"))
      (node (ref "U34") (pin "J35") (pinfunction "TCK_J35") (pintype "passive"))
    )
    (net (code "68") (name "Net-(U34A-TDI)") (class "Default")
      (node (ref "TP18") (pin "X") (pinfunction "X_X") (pintype "passive"))
      (node (ref "U34") (pin "G35") (pinfunction "TDI_G35") (pintype "passive"))
    )
    (net (code "69") (name "Net-(U34A-TDO)") (class "Default")
      (node (ref "TP17") (pin "X") (pinfunction "X_X") (pintype "passive"))
      (node (ref "U34") (pin "L35") (pinfunction "TDO_L35") (pintype "passive"))
    )
    (net (code "70") (name "Net-(U34A-TEST1)") (class "Default")
      (node (ref "R6") (pin "1") (pinfunction "1_1") (pintype "passive"))
      (node (ref "U34") (pin "L1") (pinfunction "TEST1_L1") (pintype "passive"))
    )
    (net (code "71") (name "Net-(U34A-TEST2)") (class "Default")
      (node (ref "R7") (pin "1") (pinfunction "1_1") (pintype "passive"))
      (node (ref "U34") (pin "U1") (pinfunction "TEST2_U1") (pintype "passive"))
    )
    (net (code "72") (name "Net-(U34A-TEST3)") (class "Default")
      (node (ref "R11") (pin "2") (pinfunction "2_2") (pintype "passive"))
      (node (ref "U34") (pin "V2") (pinfunction "TEST3_V2") (pintype "passive"))
    )
    (net (code "73") (name "Net-(U34A-TEST5)") (class "Default")
      (node (ref "R10") (pin "2") (pinfunction "2_2") (pintype "passive"))
      (node (ref "U34") (pin "AE1") (pinfunction "TEST5_AE1") (pintype "passive"))
    )
    (net (code "74") (name "Net-(U34A-TEST6)") (class "Default")
      (node (ref "R9") (pin "2") (pinfunction "2_2") (pintype "passive"))
      (node (ref "U34") (pin "AP20") (pinfunction "TEST6_AP20") (pintype "passive"))
    )
    (net (code "75") (name "Net-(U34A-TMS)") (class "Default")
      (node (ref "TP16") (pin "X") (pinfunction "X_X") (pintype "passive"))
      (node (ref "U34") (pin "K34") (pinfunction "TMS_K34") (pintype "passive"))
    )
    (net (code "76") (name "Net-(U34A-TRST_L)") (class "Default")
      (node (ref "R8") (pin "2") (pinfunction "2_2") (pintype "passive"))
      (node (ref "TP24") (pin "X") (pinfunction "X_X") (pintype "passive"))
      (node (ref "U34") (pin "H34") (pinfunction "TRST_L_H34") (pintype "passive"))
    )
    (net (code "77") (name "Net-(U34B-AVDD)") (class "Default")
      (node (ref "C245") (pin "2") (pinfunction "2_2") (pintype "passive"))
      (node (ref "L20") (pin "2") (pinfunction "2_2") (pintype "passive"))
      (node (ref "U34") (pin "T") (pinfunction "AVDD_T") (pintype "passive"))
    )
    (net (code "78") (name "Net-(U34B-AVDDH)") (class "Default")
      (node (ref "C239") (pin "2") (pinfunction "2_2") (pintype "passive"))
      (node (ref "L19") (pin "2") (pinfunction "2_2") (pintype "passive"))
      (node (ref "U34") (pin "A17") (pinfunction "AVDDH_A17") (pintype "passive"))
    )
    (net (code "79") (name "unconnected-(C326-Pad2)") (class "Default")
      (node (ref "C326") (pin "2") (pinfunction "2_2") (pintype "passive"))
    )
    (net (code "80") (name "unconnected-(C327-Pad2)") (class "Default")
      (node (ref "C327") (pin "2") (pinfunction "2_2") (pintype "passive"))
    )
    (net (code "81") (name "unconnected-(R143-Pad2)") (class "Default")
      (node (ref "R143") (pin "2") (pinfunction "2_2") (pintype "passive"))
    )
    (net (code "82") (name "unconnected-(U34A-CLKREQ_L[0]-PadAM34)") (class "Default")
      (node (ref "U34") (pin "AM34") (pinfunction "CLKREQ_L[0]_AM34") (pintype "passive"))
    )
    (net (code "83") (name "unconnected-(U34A-CLKREQ_L[1]-PadAN35)") (class "Default")
      (node (ref "U34") (pin "AN35") (pinfunction "CLKREQ_L[1]_AN35") (pintype "passive"))
    )
    (net (code "84") (name "unconnected-(U34A-CLKREQ_L[2]-PadAK34)") (class "Default")
      (node (ref "U34") (pin "AK34") (pinfunction "CLKREQ_L[2]_AK34") (pintype "passive"))
    )
    (net (code "85") (name "unconnected-(U34A-DWNRST_L[1]-PadG1)") (class "Default")
      (node (ref "U34") (pin "G1") (pinfunction "DWNRST_L[1]_G1") (pintype "passive"))
    )
    (net (code "86") (name "unconnected-(U34A-DWNRST_L[2]-PadK2)") (class "Default")
      (node (ref "U34") (pin "K2") (pinfunction "DWNRST_L[2]_K2") (pintype "passive"))
    )
    (net (code "87") (name "unconnected-(U34A-PERN[0]-PadB6)") (class "Default")
      (node (ref "U34") (pin "B6") (pinfunction "PERN[0]_B6") (pintype "passive"))
    )
    (net (code "88") (name "unconnected-(U34A-PERP[0]-PadB4)") (class "Default")
      (node (ref "U34") (pin "B4") (pinfunction "PERP[0]_B4") (pintype "passive"))
    )
    (net (code "89") (name "unconnected-(U34A-REFCLKI_N-PadAF34)") (class "Default")
      (node (ref "U34") (pin "AF34") (pinfunction "REFCLKI_N_AF34") (pintype "passive"))
    )
    (net (code "90") (name "unconnected-(U34A-REFCLKI_P-PadAG35)") (class "Default")
      (node (ref "U34") (pin "AG35") (pinfunction "REFCLKI_P_AG35") (pintype "passive"))
    )
    (net (code "91") (name "unconnected-(U34A-SMBUS_EN-PadAR23)") (class "Default")
      (node (ref "U34") (pin "AR23") (pinfunction "SMBUS_EN_AR23") (pintype "passive+no_connect"))
    )
    (net (code "92") (name "unconnected-(U34B-NC-PadA1)") (class "Default")
      (node (ref "U34") (pin "A1") (pinfunction "NC_A1") (pintype "passive+no_connect"))
    )
    (net (code "93") (name "unconnected-(U34B-NC-PadA3)") (class "Default")
      (node (ref "U34") (pin "A3") (pinfunction "NC_A3") (pintype "passive+no_connect"))
    )
    (net (code "94") (name "unconnected-(U34B-NC-PadA15)") (class "Default")
      (node (ref "U34") (pin "A15") (pinfunction "NC_A15") (pintype "passive+no_connect"))
    )
    (net (code "95") (name "unconnected-(U34B-NC-PadA33)") (class "Default")
      (node (ref "U34") (pin "A33") (pinfunction "NC_A33") (pintype "passive+no_connect"))
    )
    (net (code "96") (name "unconnected-(U34B-NC-PadA35)") (class "Default")
      (node (ref "U34") (pin "A35") (pinfunction "NC_A35") (pintype "passive+no_connect"))
    )
    (net (code "97") (name "unconnected-(U34B-NC-PadAB2)") (class "Default")
      (node (ref "U34") (pin "AB2") (pinfunction "NC_AB2") (pintype "passive+no_connect"))
    )
    (net (code "98") (name "unconnected-(U34B-NC-PadAD34)") (class "Default")
      (node (ref "U34") (pin "AD34") (pinfunction "NC_AD34") (pintype "passive+no_connect"))
    )
    (net (code "99") (name "unconnected-(U34B-NC-PadAE35)") (class "Default")
      (node (ref "U34") (pin "AE35") (pinfunction "NC_AE35") (pintype "passive+no_connect"))
    )
    (net (code "100") (name "unconnected-(U34B-NC-PadAJ1)") (class "Default")
      (node (ref "U34") (pin "AJ1") (pinfunction "NC_AJ1") (pintype "passive+no_connect"))
    )
    (net (code "101") (name "unconnected-(U34B-NC-PadAK2)") (class "Default")
      (node (ref "U34") (pin "AK2") (pinfunction "NC_AK2") (pintype "passive+no_connect"))
    )
    (net (code "102") (name "unconnected-(U34B-NC-PadAL1)") (class "Default")
      (node (ref "U34") (pin "AL1") (pinfunction "NC_AL1") (pintype "passive+no_connect"))
    )
    (net (code "103") (name "unconnected-(U34B-NC-PadAM2)") (class "Default")
      (node (ref "U34") (pin "AM2") (pinfunction "NC_AM2") (pintype "passive+no_connect"))
    )
    (net (code "104") (name "unconnected-(U34B-NC-PadAN1)") (class "Default")
      (node (ref "U34") (pin "AN1") (pinfunction "NC_AN1") (pintype "passive+no_connect"))
    )
    (net (code "105") (name "unconnected-(U34B-NC-PadAP1)") (class "Default")
      (node (ref "U34") (pin "AP1") (pinfunction "NC_AP1") (pintype "passive+no_connect"))
    )
    (net (code "106") (name "unconnected-(U34B-NC-PadAP2)") (class "Default")
      (node (ref "U34") (pin "AP2") (pinfunction "NC_AP2") (pintype "passive+no_connect"))
    )
    (net (code "107") (name "unconnected-(U34B-NC-PadAP4)") (class "Default")
      (node (ref "U34") (pin "AP4") (pinfunction "NC_AP4") (pintype "passive+no_connect"))
    )
    (net (code "108") (name "unconnected-(U34B-NC-PadAP16)") (class "Default")
      (node (ref "U34") (pin "AP16") (pinfunction "NC_AP16") (pintype "passive+no_connect"))
    )
    (net (code "109") (name "unconnected-(U34B-NC-PadAP24)") (class "Default")
      (node (ref "U34") (pin "AP24") (pinfunction "NC_AP24") (pintype "passive+no_connect"))
    )
    (net (code "110") (name "unconnected-(U34B-NC-PadAP26)") (class "Default")
      (node (ref "U34") (pin "AP26") (pinfunction "NC_AP26") (pintype "passive+no_connect"))
    )
    (net (code "111") (name "unconnected-(U34B-NC-PadAP32)") (class "Default")
      (node (ref "U34") (pin "AP32") (pinfunction "NC_AP32") (pintype "passive+no_connect"))
    )
    (net (code "112") (name "unconnected-(U34B-NC-PadAP34)") (class "Default")
      (node (ref "U34") (pin "AP34") (pinfunction "NC_AP34") (pintype "passive+no_connect"))
    )
    (net (code "113") (name "unconnected-(U34B-NC-PadAP35)") (class "Default")
      (node (ref "U34") (pin "AP35") (pinfunction "NC_AP35") (pintype "passive+no_connect"))
    )
    (net (code "114") (name "unconnected-(U34B-NC-PadAR1)") (class "Default")
      (node (ref "U34") (pin "AR1") (pinfunction "NC_AR1") (pintype "passive+no_connect"))
    )
    (net (code "115") (name "unconnected-(U34B-NC-PadAR3)") (class "Default")
      (node (ref "U34") (pin "AR3") (pinfunction "NC_AR3") (pintype "passive+no_connect"))
    )
    (net (code "116") (name "unconnected-(U34B-NC-PadAR17)") (class "Default")
      (node (ref "U34") (pin "AR17") (pinfunction "NC_AR17") (pintype "passive+no_connect"))
    )
    (net (code "117") (name "unconnected-(U34B-NC-PadAR21)") (class "Default")
      (node (ref "U34") (pin "AR21") (pinfunction "NC_AR21") (pintype "passive+no_connect"))
    )
    (net (code "118") (name "unconnected-(U34B-NC-PadAR25)") (class "Default")
      (node (ref "U34") (pin "AR25") (pinfunction "NC_AR25") (pintype "passive+no_connect"))
    )
    (net (code "119") (name "unconnected-(U34B-NC-PadAR27)") (class "Default")
      (node (ref "U34") (pin "AR27") (pinfunction "NC_AR27") (pintype "passive+no_connect"))
    )
    (net (code "120") (name "unconnected-(U34B-NC-PadAR29)") (class "Default")
      (node (ref "U34") (pin "AR29") (pinfunction "NC_AR29") (pintype "passive+no_connect"))
    )
    (net (code "121") (name "unconnected-(U34B-NC-PadAR33)") (class "Default")
      (node (ref "U34") (pin "AR33") (pinfunction "NC_AR33") (pintype "passive+no_connect"))
    )
    (net (code "122") (name "unconnected-(U34B-NC-PadAR35)") (class "Default")
      (node (ref "U34") (pin "AR35") (pinfunction "NC_AR35") (pintype "passive+no_connect"))
    )
    (net (code "123") (name "unconnected-(U34B-NC-PadB1)") (class "Default")
      (node (ref "U34") (pin "B1") (pinfunction "NC_B1") (pintype "passive+no_connect"))
    )
    (net (code "124") (name "unconnected-(U34B-NC-PadB2)") (class "Default")
      (node (ref "U34") (pin "B2") (pinfunction "NC_B2") (pintype "passive+no_connect"))
    )
    (net (code "125") (name "unconnected-(U34B-NC-PadB8)") (class "Default")
      (node (ref "U34") (pin "B8") (pinfunction "NC_B8") (pintype "passive+no_connect"))
    )
    (net (code "126") (name "unconnected-(U34B-NC-PadB12)") (class "Default")
      (node (ref "U34") (pin "B12") (pinfunction "NC_B12") (pintype "passive+no_connect"))
    )
    (net (code "127") (name "unconnected-(U34B-NC-PadB20)") (class "Default")
      (node (ref "U34") (pin "B20") (pinfunction "NC_B20") (pintype "passive+no_connect"))
    )
    (net (code "128") (name "unconnected-(U34B-NC-PadB24)") (class "Default")
      (node (ref "U34") (pin "B24") (pinfunction "NC_B24") (pintype "passive+no_connect"))
    )
    (net (code "129") (name "unconnected-(U34B-NC-PadB28)") (class "Default")
      (node (ref "U34") (pin "B28") (pinfunction "NC_B28") (pintype "passive+no_connect"))
    )
    (net (code "130") (name "unconnected-(U34B-NC-PadB34)") (class "Default")
      (node (ref "U34") (pin "B34") (pinfunction "NC_B34") (pintype "passive+no_connect"))
    )
    (net (code "131") (name "unconnected-(U34B-NC-PadB35)") (class "Default")
      (node (ref "U34") (pin "B35") (pinfunction "NC_B35") (pintype "passive+no_connect"))
    )
    (net (code "132") (name "unconnected-(U34B-NC-PadC1)") (class "Default")
      (node (ref "U34") (pin "C1") (pinfunction "NC_C1") (pintype "passive+no_connect"))
    )
    (net (code "133") (name "unconnected-(U34B-NC-PadC35)") (class "Default")
      (node (ref "U34") (pin "C35") (pinfunction "NC_C35") (pintype "passive+no_connect"))
    )
    (net (code "134") (name "unconnected-(U34B-NC-PadD2)") (class "Default")
      (node (ref "U34") (pin "D2") (pinfunction "NC_D2") (pintype "passive+no_connect"))
    )
    (net (code "135") (name "unconnected-(U34B-NC-PadD34)") (class "Default")
      (node (ref "U34") (pin "D34") (pinfunction "NC_D34") (pintype "passive+no_connect"))
    )
    (net (code "136") (name "unconnected-(U34B-NC-PadE1)") (class "Default")
      (node (ref "U34") (pin "E1") (pinfunction "NC_E1") (pintype "passive+no_connect"))
    )
    (net (code "137") (name "unconnected-(U34B-NC-PadE35)") (class "Default")
      (node (ref "U34") (pin "E35") (pinfunction "NC_E35") (pintype "passive+no_connect"))
    )
    (net (code "138") (name "unconnected-(U34B-NC-PadH2)") (class "Default")
      (node (ref "U34") (pin "H2") (pinfunction "NC_H2") (pintype "passive+no_connect"))
    )
    (net (code "139") (name "unconnected-(U34B-NC-PadJ1)") (class "Default")
      (node (ref "U34") (pin "J1") (pinfunction "NC_J1") (pintype "passive+no_connect"))
    )
    (net (code "140") (name "unconnected-(U34B-NC-PadM34)") (class "Default")
      (node (ref "U34") (pin "M34") (pinfunction "NC_M34") (pintype "passive+no_connect"))
    )
  )
)
